# 4_USB.net
KiCad netlist of a schematic drawn in Altium Designer
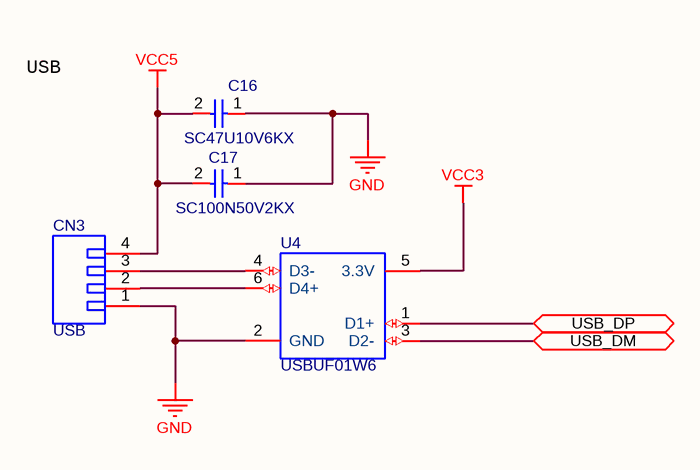
[diagram p0: 4_USB.SchDoc]

(export (version "E")
  (design (tool "Eeschema 10.0.6"))
  (components
    (comp (ref "C16")
      (value "SC47U10V6KX")
      (footprint "CAPC1206(3216)")
      (description "CAP 47uF 10V ±10% 1206(3216 Metric) Thickness 1.8mm SMD")
      (libsource (lib "PUMAlib") (part "CAP(1206)47UF10V"))
    )
    (comp (ref "C17")
      (value "SC100N50V2KX")
      (footprint "CAPC0402(1005)60_L")
      (description "CAP 100nF 50V ±10% 0402 (1005 Metric) Thickness 0.6mm SMD")
      (libsource (lib "PUMAlib") (part "CAP(0402)100nF50V"))
    )
    (comp (ref "CN3")
      (value "USB")
      (footprint "4PHEADERS-2D54")
      (description "4 holes for 18awg wire")
      (fields (field (name "MANUFACTURER") "JST"))
      (libsource (lib "PUMAlib") (part "4PIN-CN"))
    )
    (comp (ref "U4")
      (value "USBUF01W6")
      (footprint "SOT323-6L")
      (libsource (lib "PUMAlib") (part "USBUF01W6"))
    )
  )
  (nets
    (net (code "1") (name "/USB_DM") (class "Default")
      (node (ref "U4") (pin "3") (pinfunction "D2-_3") (pintype "bidirectional"))
    )
    (net (code "2") (name "/USB_DP") (class "Default")
      (node (ref "U4") (pin "1") (pinfunction "D1+_1") (pintype "bidirectional"))
    )
    (net (code "3") (name "GND") (class "Default")
      (node (ref "C16") (pin "1") (pinfunction "1_1") (pintype "passive"))
      (node (ref "C17") (pin "1") (pinfunction "1_1") (pintype "passive"))
      (node (ref "CN3") (pin "1") (pinfunction "1_1") (pintype "passive"))
      (node (ref "U4") (pin "2") (pinfunction "GND_2") (pintype "power_in"))
    )
    (net (code "4") (name "Net-(U4-D3-)") (class "Default")
      (node (ref "CN3") (pin "3") (pinfunction "3_3") (pintype "passive"))
      (node (ref "U4") (pin "4") (pinfunction "D3-_4") (pintype "bidirectional"))
    )
    (net (code "5") (name "Net-(U4-D4+)") (class "Default")
      (node (ref "CN3") (pin "2") (pinfunction "2_2") (pintype "passive"))
      (node (ref "U4") (pin "6") (pinfunction "D4+_6") (pintype "bidirectional"))
    )
    (net (code "6") (name "VCC3") (class "Default")
      (node (ref "U4") (pin "5") (pinfunction "3.3V_5") (pintype "power_in"))
    )
    (net (code "7") (name "VCC5") (class "Default")
      (node (ref "C16") (pin "2") (pinfunction "2_2") (pintype "passive"))
      (node (ref "C17") (pin "2") (pinfunction "2_2") (pintype "passive"))
      (node (ref "CN3") (pin "4") (pinfunction "4_4") (pintype "passive"))
    )
  )
)
